# pumpbox-v4.net
KiCad netlist of a schematic drawn in EAGLE
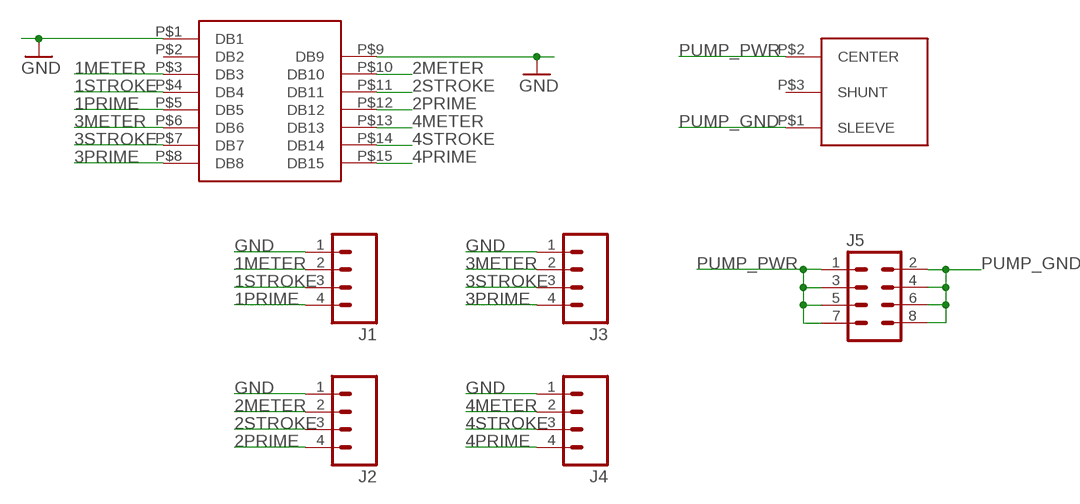
[diagram p0: schematic, sheet 1]

(export (version "E")
  (design (tool "Eeschema 10.0.6"))
  (components
    (comp (ref "J1")
      (value "M04PTH")
      (footprint "eagle-import:1X04")
      (libsource (lib "eagle-import") (part "M04PTH"))
    )
    (comp (ref "J2")
      (value "M04PTH")
      (footprint "eagle-import:1X04")
      (libsource (lib "eagle-import") (part "M04PTH"))
    )
    (comp (ref "J3")
      (value "M04PTH")
      (footprint "eagle-import:1X04")
      (libsource (lib "eagle-import") (part "M04PTH"))
    )
    (comp (ref "J4")
      (value "M04PTH")
      (footprint "eagle-import:1X04")
      (libsource (lib "eagle-import") (part "M04PTH"))
    )
    (comp (ref "J5")
      (value "M04X2")
      (footprint "eagle-import:2X4")
      (libsource (lib "eagle-import") (part "M04X2"))
    )
    (comp (ref "U$1")
      (value "DB15")
      (footprint "eagle-import:DB15")
      (libsource (lib "eagle-import") (part "DB15"))
    )
    (comp (ref "U$2")
      (value "RAPC10P")
      (footprint "eagle-import:RAPC10P")
      (libsource (lib "eagle-import") (part "RAPC10P"))
    )
  )
  (nets
    (net (code "1") (name "/1METER") (class "Default")
      (node (ref "J1") (pin "2") (pinfunction "2_2") (pintype "passive"))
      (node (ref "U$1") (pin "P$3") (pinfunction "DB3_P$3") (pintype "bidirectional"))
    )
    (net (code "2") (name "/1PRIME") (class "Default")
      (node (ref "J1") (pin "4") (pinfunction "4_4") (pintype "passive"))
      (node (ref "U$1") (pin "P$5") (pinfunction "DB5_P$5") (pintype "bidirectional"))
    )
    (net (code "3") (name "/1STROKE") (class "Default")
      (node (ref "J1") (pin "3") (pinfunction "3_3") (pintype "passive"))
      (node (ref "U$1") (pin "P$4") (pinfunction "DB4_P$4") (pintype "bidirectional"))
    )
    (net (code "4") (name "/2METER") (class "Default")
      (node (ref "J2") (pin "2") (pinfunction "2_2") (pintype "passive"))
      (node (ref "U$1") (pin "P$10") (pinfunction "DB10_P$10") (pintype "bidirectional"))
    )
    (net (code "5") (name "/2PRIME") (class "Default")
      (node (ref "J2") (pin "4") (pinfunction "4_4") (pintype "passive"))
      (node (ref "U$1") (pin "P$12") (pinfunction "DB12_P$12") (pintype "bidirectional"))
    )
    (net (code "6") (name "/2STROKE") (class "Default")
      (node (ref "J2") (pin "3") (pinfunction "3_3") (pintype "passive"))
      (node (ref "U$1") (pin "P$11") (pinfunction "DB11_P$11") (pintype "bidirectional"))
    )
    (net (code "7") (name "/3METER") (class "Default")
      (node (ref "J3") (pin "2") (pinfunction "2_2") (pintype "passive"))
      (node (ref "U$1") (pin "P$6") (pinfunction "DB6_P$6") (pintype "bidirectional"))
    )
    (net (code "8") (name "/3PRIME") (class "Default")
      (node (ref "J3") (pin "4") (pinfunction "4_4") (pintype "passive"))
      (node (ref "U$1") (pin "P$8") (pinfunction "DB8_P$8") (pintype "bidirectional"))
    )
    (net (code "9") (name "/3STROKE") (class "Default")
      (node (ref "J3") (pin "3") (pinfunction "3_3") (pintype "passive"))
      (node (ref "U$1") (pin "P$7") (pinfunction "DB7_P$7") (pintype "bidirectional"))
    )
    (net (code "10") (name "/4METER") (class "Default")
      (node (ref "J4") (pin "2") (pinfunction "2_2") (pintype "passive"))
      (node (ref "U$1") (pin "P$13") (pinfunction "DB13_P$13") (pintype "bidirectional"))
    )
    (net (code "11") (name "/4PRIME") (class "Default")
      (node (ref "J4") (pin "4") (pinfunction "4_4") (pintype "passive"))
      (node (ref "U$1") (pin "P$15") (pinfunction "DB15_P$15") (pintype "bidirectional"))
    )
    (net (code "12") (name "/4STROKE") (class "Default")
      (node (ref "J4") (pin "3") (pinfunction "3_3") (pintype "passive"))
      (node (ref "U$1") (pin "P$14") (pinfunction "DB14_P$14") (pintype "bidirectional"))
    )
    (net (code "13") (name "/PUMP_GND") (class "Default")
      (node (ref "J5") (pin "2") (pinfunction "2_2") (pintype "passive"))
      (node (ref "J5") (pin "4") (pinfunction "4_4") (pintype "passive"))
      (node (ref "J5") (pin "6") (pinfunction "6_6") (pintype "passive"))
      (node (ref "J5") (pin "8") (pinfunction "8_8") (pintype "passive"))
      (node (ref "U$2") (pin "P$1") (pinfunction "SLEEVE_P$1") (pintype "bidirectional"))
    )
    (net (code "14") (name "/PUMP_PWR") (class "Default")
      (node (ref "J5") (pin "1") (pinfunction "1_1") (pintype "passive"))
      (node (ref "J5") (pin "3") (pinfunction "3_3") (pintype "passive"))
      (node (ref "J5") (pin "5") (pinfunction "5_5") (pintype "passive"))
      (node (ref "J5") (pin "7") (pinfunction "7_7") (pintype "passive"))
      (node (ref "U$2") (pin "P$2") (pinfunction "CENTER_P$2") (pintype "bidirectional"))
    )
    (net (code "15") (name "GND") (class "Default")
      (node (ref "J1") (pin "1") (pinfunction "1_1") (pintype "passive"))
      (node (ref "J2") (pin "1") (pinfunction "1_1") (pintype "passive"))
      (node (ref "J3") (pin "1") (pinfunction "1_1") (pintype "passive"))
      (node (ref "J4") (pin "1") (pinfunction "1_1") (pintype "passive"))
      (node (ref "U$1") (pin "P$1") (pinfunction "DB1_P$1") (pintype "bidirectional"))
      (node (ref "U$1") (pin "P$9") (pinfunction "DB9_P$9") (pintype "bidirectional"))
    )
    (net (code "16") (name "unconnected-(U$1-DB2-PadP$2)") (class "Default")
      (node (ref "U$1") (pin "P$2") (pinfunction "DB2_P$2") (pintype "bidirectional"))
    )
    (net (code "17") (name "unconnected-(U$2-SHUNT-PadP$3)") (class "Default")
      (node (ref "U$2") (pin "P$3") (pinfunction "SHUNT_P$3") (pintype "bidirectional"))
    )
  )
)
